# Motor_Control.net
KiCad netlist of a schematic drawn in Altium Designer
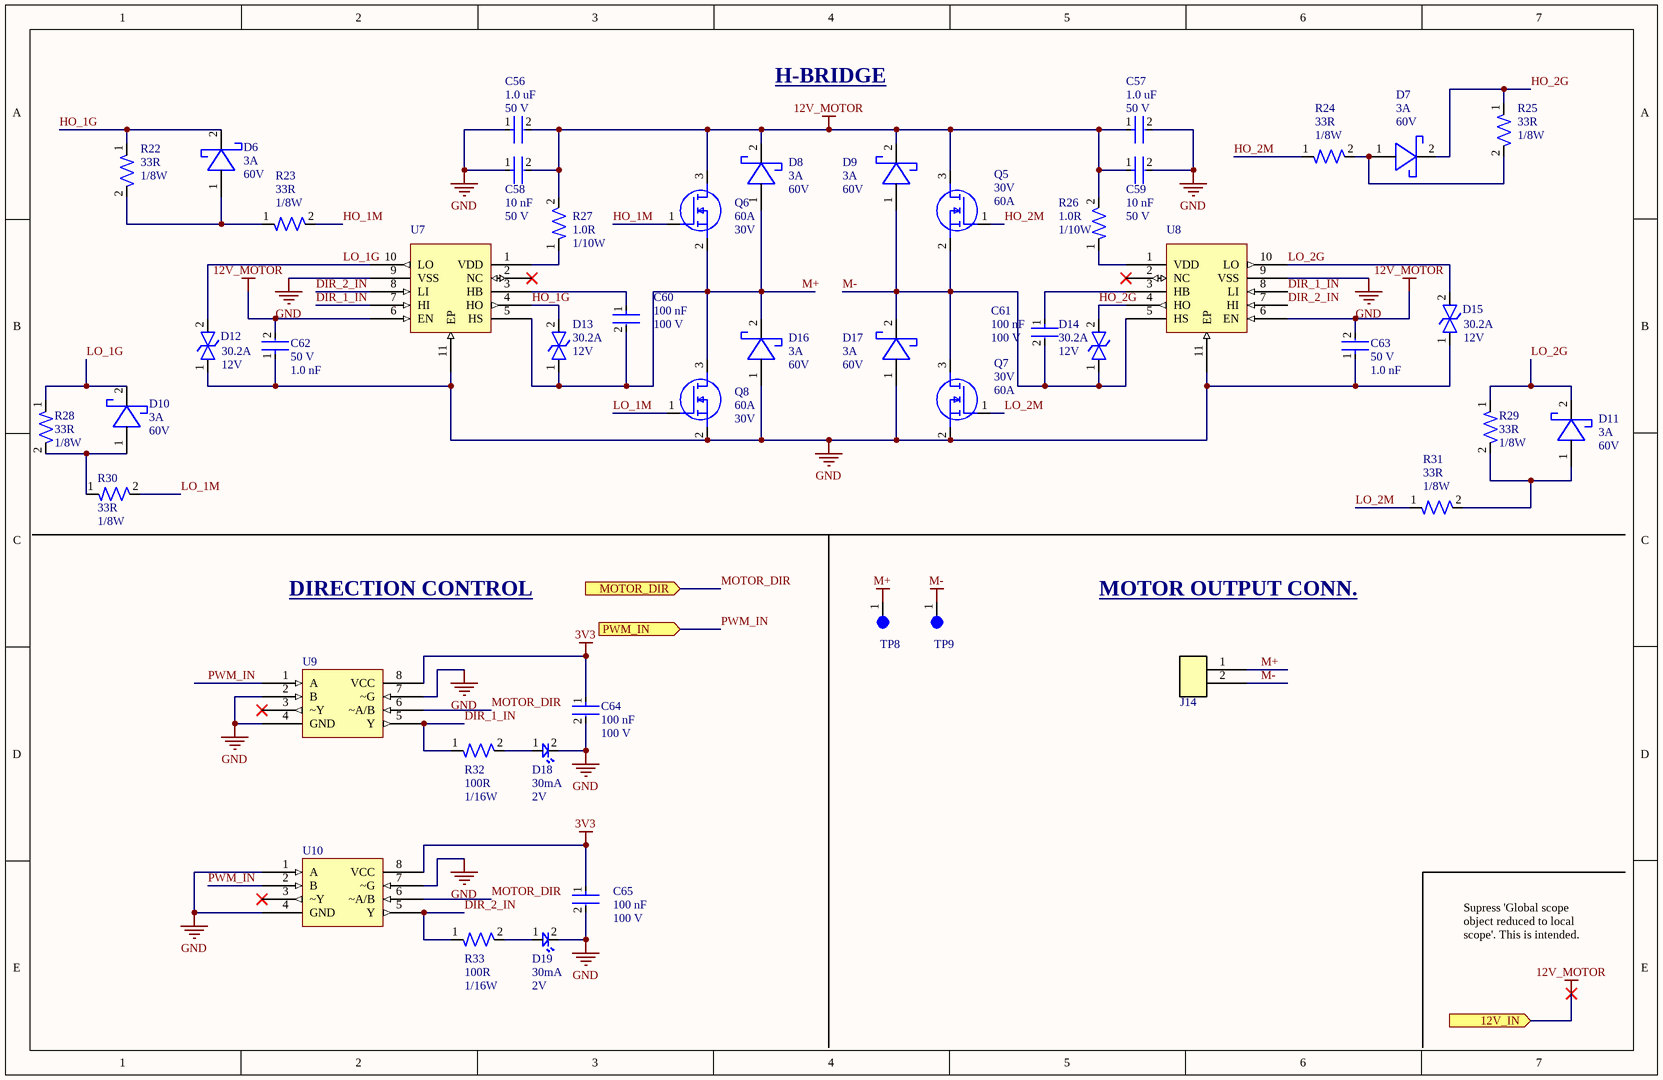
[diagram p0: Motor_Control.SchDoc]

(export (version "E")
  (design (tool "Eeschema 10.0.6"))
  (components
    (comp (ref "C56")
      (value "CC0805KKX7R9BB105")
      (footprint "CAP-0805")
      (description "CAP CER 1UF 50V X7R 0805")
      (fields (field (name "VOLTAGE") "50 V") (field (name "CAPACITANCE") "1.0 uF"))
      (libsource (lib "JLC_25") (part "CAP-1U-0001"))
    )
    (comp (ref "C57")
      (value "CC0805KKX7R9BB105")
      (footprint "CAP-0805")
      (description "CAP CER 1UF 50V X7R 0805")
      (fields (field (name "VOLTAGE") "50 V") (field (name "CAPACITANCE") "1.0 uF"))
      (libsource (lib "JLC_25") (part "CAP-1U-0001"))
    )
    (comp (ref "C58")
      (value "CC0603KPX7R9BB103")
      (footprint "CAP-0603")
      (description "CAP CER 10000PF 50V X7R 0603")
      (fields (field (name "VOLTAGE") "50 V") (field (name "CAPACITANCE") "10 nF"))
      (libsource (lib "JLC_25") (part "CAP-10N-0002"))
    )
    (comp (ref "C59")
      (value "CC0603KPX7R9BB103")
      (footprint "CAP-0603")
      (description "CAP CER 10000PF 50V X7R 0603")
      (fields (field (name "VOLTAGE") "50 V") (field (name "CAPACITANCE") "10 nF"))
      (libsource (lib "JLC_25") (part "CAP-10N-0002"))
    )
    (comp (ref "C60")
      (value "CC0603KRX7R0BB104")
      (footprint "CAP-0603")
      (description "CAP CER 0.1UF 100V X7R 0603")
      (fields (field (name "CAPACITANCE") "100 nF") (field (name "VOLTAGE") "100 V"))
      (libsource (lib "JLC_25") (part "CAP-100N-0001"))
    )
    (comp (ref "C61")
      (value "CC0603KRX7R0BB104")
      (footprint "CAP-0603")
      (description "CAP CER 0.1UF 100V X7R 0603")
      (fields (field (name "CAPACITANCE") "100 nF") (field (name "VOLTAGE") "100 V"))
      (libsource (lib "JLC_25") (part "CAP-100N-0001"))
    )
    (comp (ref "C62")
      (value "CC0402KRX7R9BB102")
      (footprint "CAP-0402")
      (description "CAP CER 1000PF 50V X7R 0402")
      (fields (field (name "VOLTAGE") "50 V") (field (name "CAPACITANCE") "1.0 nF"))
      (libsource (lib "JLC_25") (part "CAP-1N-0001"))
    )
    (comp (ref "C63")
      (value "CC0402KRX7R9BB102")
      (footprint "CAP-0402")
      (description "CAP CER 1000PF 50V X7R 0402")
      (fields (field (name "VOLTAGE") "50 V") (field (name "CAPACITANCE") "1.0 nF"))
      (libsource (lib "JLC_25") (part "CAP-1N-0001"))
    )
    (comp (ref "C64")
      (value "CC0603KRX7R0BB104")
      (footprint "CAP-0603")
      (description "CAP CER 0.1UF 100V X7R 0603")
      (fields (field (name "CAPACITANCE") "100 nF") (field (name "VOLTAGE") "100 V"))
      (libsource (lib "JLC_25") (part "CAP-100N-0001"))
    )
    (comp (ref "C65")
      (value "CC0603KRX7R0BB104")
      (footprint "CAP-0603")
      (description "CAP CER 0.1UF 100V X7R 0603")
      (fields (field (name "CAPACITANCE") "100 nF") (field (name "VOLTAGE") "100 V"))
      (libsource (lib "JLC_25") (part "CAP-100N-0001"))
    )
    (comp (ref "D6")
      (value "PMEG6030EP,115")
      (footprint "DIO-SOD128")
      (description "DIODE SCHOTTKY 60V 3A SOD128")
      (fields (field (name "CURRENT RATING") "3A") (field (name "REVERSE VOLTAGE") "60V"))
      (libsource (lib "JLC_25") (part "DIO-SCHOTTKY-0003"))
    )
    (comp (ref "D7")
      (value "PMEG6030EP,115")
      (footprint "DIO-SOD128")
      (description "DIODE SCHOTTKY 60V 3A SOD128")
      (fields (field (name "CURRENT RATING") "3A") (field (name "REVERSE VOLTAGE") "60V"))
      (libsource (lib "JLC_25") (part "DIO-SCHOTTKY-0003"))
    )
    (comp (ref "D8")
      (value "PMEG6030EP,115")
      (footprint "DIO-SOD128")
      (description "DIODE SCHOTTKY 60V 3A SOD128")
      (fields (field (name "CURRENT RATING") "3A") (field (name "REVERSE VOLTAGE") "60V"))
      (libsource (lib "JLC_25") (part "DIO-SCHOTTKY-0003"))
    )
    (comp (ref "D9")
      (value "PMEG6030EP,115")
      (footprint "DIO-SOD128")
      (description "DIODE SCHOTTKY 60V 3A SOD128")
      (fields (field (name "CURRENT RATING") "3A") (field (name "REVERSE VOLTAGE") "60V"))
      (libsource (lib "JLC_25") (part "DIO-SCHOTTKY-0003"))
    )
    (comp (ref "D10")
      (value "PMEG6030EP,115")
      (footprint "DIO-SOD128")
      (description "DIODE SCHOTTKY 60V 3A SOD128")
      (fields (field (name "CURRENT RATING") "3A") (field (name "REVERSE VOLTAGE") "60V"))
      (libsource (lib "JLC_25") (part "DIO-SCHOTTKY-0003"))
    )
    (comp (ref "D11")
      (value "PMEG6030EP,115")
      (footprint "DIO-SOD128")
      (description "DIODE SCHOTTKY 60V 3A SOD128")
      (fields (field (name "CURRENT RATING") "3A") (field (name "REVERSE VOLTAGE") "60V"))
      (libsource (lib "JLC_25") (part "DIO-SCHOTTKY-0003"))
    )
    (comp (ref "D12")
      (value "SMBJ12CA")
      (footprint "DO-214AA (SMBJ)")
      (description "TVS DIODE 12VWM 19.9VC DO214AA")
      (fields (field (name "STANDOFF VOLTAGE") "12V") (field (name "CURRENT RATING") "30.2A"))
      (libsource (lib "JLC_25") (part "DIO-TVS-0002"))
    )
    (comp (ref "D13")
      (value "SMBJ12CA")
      (footprint "DO-214AA (SMBJ)")
      (description "TVS DIODE 12VWM 19.9VC DO214AA")
      (fields (field (name "STANDOFF VOLTAGE") "12V") (field (name "CURRENT RATING") "30.2A"))
      (libsource (lib "JLC_25") (part "DIO-TVS-0002"))
    )
    (comp (ref "D14")
      (value "SMBJ12CA")
      (footprint "DO-214AA (SMBJ)")
      (description "TVS DIODE 12VWM 19.9VC DO214AA")
      (fields (field (name "STANDOFF VOLTAGE") "12V") (field (name "CURRENT RATING") "30.2A"))
      (libsource (lib "JLC_25") (part "DIO-TVS-0002"))
    )
    (comp (ref "D15")
      (value "SMBJ12CA")
      (footprint "DO-214AA (SMBJ)")
      (description "TVS DIODE 12VWM 19.9VC DO214AA")
      (fields (field (name "STANDOFF VOLTAGE") "12V") (field (name "CURRENT RATING") "30.2A"))
      (libsource (lib "JLC_25") (part "DIO-TVS-0002"))
    )
    (comp (ref "D16")
      (value "PMEG6030EP,115")
      (footprint "DIO-SOD128")
      (description "DIODE SCHOTTKY 60V 3A SOD128")
      (fields (field (name "CURRENT RATING") "3A") (field (name "REVERSE VOLTAGE") "60V"))
      (libsource (lib "JLC_25") (part "DIO-SCHOTTKY-0003"))
    )
    (comp (ref "D17")
      (value "PMEG6030EP,115")
      (footprint "DIO-SOD128")
      (description "DIODE SCHOTTKY 60V 3A SOD128")
      (fields (field (name "CURRENT RATING") "3A") (field (name "REVERSE VOLTAGE") "60V"))
      (libsource (lib "JLC_25") (part "DIO-SCHOTTKY-0003"))
    )
    (comp (ref "D18")
      (value "BL-HKC36G-AV-TRB")
      (footprint "LED-0603")
      (description "LED YELLOW CLEAR 0603 SMD")
      (fields (field (name "FORWARD CURRENT") "30mA") (field (name "FORWARD VOLTAGE") "2V"))
      (libsource (lib "JLC_25") (part "LED-0001"))
    )
    (comp (ref "D19")
      (value "BL-HKC36G-AV-TRB")
      (footprint "LED-0603")
      (description "LED YELLOW CLEAR 0603 SMD")
      (fields (field (name "FORWARD CURRENT") "30mA") (field (name "FORWARD VOLTAGE") "2V"))
      (libsource (lib "JLC_25") (part "LED-0001"))
    )
    (comp (ref "J14")
      (value "0430450212")
      (footprint "CONN-2POS-0001")
      (description "CONN HEADER VERT 2POS")
      (libsource (lib "JLC_25") (part "CONN-2POS-0001"))
    )
    (comp (ref "Q5")
      (value "CSD17575Q3")
      (footprint "IC-8VSONCLIP")
      (description "MOSFET N-CH 30V 60A 8VSON")
      (fields (field (name "VOLTAGE") "30V") (field (name "CONTINUOUS CURRENT") "60A"))
      (libsource (lib "JLC_25") (part "NMOS-26A-0001"))
    )
    (comp (ref "Q6")
      (value "CSD17575Q3")
      (footprint "IC-8VSONCLIP")
      (description "MOSFET N-CH 30V 60A 8VSON")
      (fields (field (name "VOLTAGE") "30V") (field (name "CONTINUOUS CURRENT") "60A"))
      (libsource (lib "JLC_25") (part "NMOS-26A-0001"))
    )
    (comp (ref "Q7")
      (value "CSD17575Q3")
      (footprint "IC-8VSONCLIP")
      (description "MOSFET N-CH 30V 60A 8VSON")
      (fields (field (name "VOLTAGE") "30V") (field (name "CONTINUOUS CURRENT") "60A"))
      (libsource (lib "JLC_25") (part "NMOS-26A-0001"))
    )
    (comp (ref "Q8")
      (value "CSD17575Q3")
      (footprint "IC-8VSONCLIP")
      (description "MOSFET N-CH 30V 60A 8VSON")
      (fields (field (name "VOLTAGE") "30V") (field (name "CONTINUOUS CURRENT") "60A"))
      (libsource (lib "JLC_25") (part "NMOS-26A-0001"))
    )
    (comp (ref "R22")
      (value "RC0402FR-7W33RL")
      (footprint "RES-0402")
      (description "RES 33 OHM 1% 1/8W 0402")
      (fields (field (name "TOLERANCE") "1%") (field (name "RESISTANCE") "33R") (field (name "POWER") "1/8W"))
      (libsource (lib "JLC_25") (part "RES-33-0001"))
    )
    (comp (ref "R23")
      (value "RC0402FR-7W33RL")
      (footprint "RES-0402")
      (description "RES 33 OHM 1% 1/8W 0402")
      (fields (field (name "TOLERANCE") "1%") (field (name "RESISTANCE") "33R") (field (name "POWER") "1/8W"))
      (libsource (lib "JLC_25") (part "RES-33-0001"))
    )
    (comp (ref "R24")
      (value "RC0402FR-7W33RL")
      (footprint "RES-0402")
      (description "RES 33 OHM 1% 1/8W 0402")
      (fields (field (name "TOLERANCE") "1%") (field (name "RESISTANCE") "33R") (field (name "POWER") "1/8W"))
      (libsource (lib "JLC_25") (part "RES-33-0001"))
    )
    (comp (ref "R25")
      (value "RC0402FR-7W33RL")
      (footprint "RES-0402")
      (description "RES 33 OHM 1% 1/8W 0402")
      (fields (field (name "TOLERANCE") "1%") (field (name "RESISTANCE") "33R") (field (name "POWER") "1/8W"))
      (libsource (lib "JLC_25") (part "RES-33-0001"))
    )
    (comp (ref "R26")
      (value "ERJ2GEJ1R0X")
      (footprint "RES-0402")
      (description "RES SMD 1 OHM 5% 1/10W 0402")
      (fields
        (field (name "TOLERANCE") "5%")
        (field (name "RESISTANCE") "1.0R")
        (field (name "POWER") "1/10W")
      )
      (libsource (lib "JLC_25") (part "RES-1-0001"))
    )
    (comp (ref "R27")
      (value "ERJ2GEJ1R0X")
      (footprint "RES-0402")
      (description "RES SMD 1 OHM 5% 1/10W 0402")
      (fields
        (field (name "TOLERANCE") "5%")
        (field (name "RESISTANCE") "1.0R")
        (field (name "POWER") "1/10W")
      )
      (libsource (lib "JLC_25") (part "RES-1-0001"))
    )
    (comp (ref "R28")
      (value "RC0402FR-7W33RL")
      (footprint "RES-0402")
      (description "RES 33 OHM 1% 1/8W 0402")
      (fields (field (name "TOLERANCE") "1%") (field (name "RESISTANCE") "33R") (field (name "POWER") "1/8W"))
      (libsource (lib "JLC_25") (part "RES-33-0001"))
    )
    (comp (ref "R29")
      (value "RC0402FR-7W33RL")
      (footprint "RES-0402")
      (description "RES 33 OHM 1% 1/8W 0402")
      (fields (field (name "TOLERANCE") "1%") (field (name "RESISTANCE") "33R") (field (name "POWER") "1/8W"))
      (libsource (lib "JLC_25") (part "RES-33-0001"))
    )
    (comp (ref "R30")
      (value "RC0402FR-7W33RL")
      (footprint "RES-0402")
      (description "RES 33 OHM 1% 1/8W 0402")
      (fields (field (name "TOLERANCE") "1%") (field (name "RESISTANCE") "33R") (field (name "POWER") "1/8W"))
      (libsource (lib "JLC_25") (part "RES-33-0001"))
    )
    (comp (ref "R31")
      (value "RC0402FR-7W33RL")
      (footprint "RES-0402")
      (description "RES 33 OHM 1% 1/8W 0402")
      (fields (field (name "TOLERANCE") "1%") (field (name "RESISTANCE") "33R") (field (name "POWER") "1/8W"))
      (libsource (lib "JLC_25") (part "RES-33-0001"))
    )
    (comp (ref "R32")
      (value "RC0402FR-07100RL")
      (footprint "RES-0402")
      (description "RES 100 OHM 1% 1/16W 0402")
      (fields
        (field (name "TOLERANCE") "1%")
        (field (name "POWER") "1/16W")
        (field (name "RESISTANCE") "100R")
      )
      (libsource (lib "JLC_25") (part "RES-100-0001"))
    )
    (comp (ref "R33")
      (value "RC0402FR-07100RL")
      (footprint "RES-0402")
      (description "RES 100 OHM 1% 1/16W 0402")
      (fields
        (field (name "TOLERANCE") "1%")
        (field (name "POWER") "1/16W")
        (field (name "RESISTANCE") "100R")
      )
      (libsource (lib "JLC_25") (part "RES-100-0001"))
    )
    (comp (ref "TP8")
      (value "5003")
      (footprint "TEST-POINT-0001")
      (description "Oranange PC Test Point, Miniature Phoisphor Bronze Silver Plating Through Hole Mounting Type")
      (libsource (lib "*") (part "TEST-POINT-0001"))
    )
    (comp (ref "TP9")
      (value "5003")
      (footprint "TEST-POINT-0001")
      (description "Oranange PC Test Point, Miniature Phoisphor Bronze Silver Plating Through Hole Mounting Type")
      (libsource (lib "*") (part "TEST-POINT-0001"))
    )
    (comp (ref "U7")
      (value "UCC27282DRCR")
      (footprint "IC-10VSON")
      (description "IC GATE DRVR HALF-BRIDGE 10VSON")
      (libsource (lib "") (part "IC-GTDR-0001_1"))
    )
    (comp (ref "U8")
      (value "UCC27282DRCR")
      (footprint "IC-10VSON")
      (description "IC GATE DRVR HALF-BRIDGE 10VSON")
      (libsource (lib "JLC_25") (part "IC-GTDR-0001"))
    )
    (comp (ref "U9")
      (value "SN74LVC2G157DCUR")
      (footprint "IC-8VSSOP")
      (description "Multiplexer 1 x 2:1 8-VSSOP")
      (libsource (lib "JLC_25") (part "IC-MUX-0001"))
    )
    (comp (ref "U10")
      (value "SN74LVC2G157DCUR")
      (footprint "IC-8VSSOP")
      (description "Multiplexer 1 x 2:1 8-VSSOP")
      (libsource (lib "JLC_25") (part "IC-MUX-0001"))
    )
  )
  (nets
    (net (code "1") (name "/DIR_1_IN") (class "Default")
      (node (ref "R32") (pin "1") (pinfunction "1_1") (pintype "passive"))
      (node (ref "U7") (pin "7") (pinfunction "HI_7") (pintype "input"))
      (node (ref "U8") (pin "8") (pinfunction "LI_8") (pintype "input"))
      (node (ref "U9") (pin "5") (pinfunction "Y_5") (pintype "output"))
    )
    (net (code "2") (name "/DIR_2_IN") (class "Default")
      (node (ref "R33") (pin "1") (pinfunction "1_1") (pintype "passive"))
      (node (ref "U10") (pin "5") (pinfunction "Y_5") (pintype "output"))
      (node (ref "U7") (pin "8") (pinfunction "LI_8") (pintype "input"))
      (node (ref "U8") (pin "7") (pinfunction "HI_7") (pintype "input"))
    )
    (net (code "3") (name "/HO_1G") (class "Default")
      (node (ref "D13") (pin "2") (pintype "passive"))
      (node (ref "D6") (pin "2") (pinfunction "ANODE_2") (pintype "passive"))
      (node (ref "R22") (pin "1") (pinfunction "1_1") (pintype "passive"))
      (node (ref "U7") (pin "4") (pinfunction "HO_4") (pintype "output"))
    )
    (net (code "4") (name "/HO_1M") (class "Default")
      (node (ref "Q6") (pin "1") (pinfunction "G_1") (pintype "passive"))
      (node (ref "R23") (pin "2") (pinfunction "2_2") (pintype "passive"))
    )
    (net (code "5") (name "/HO_2G") (class "Default")
      (node (ref "D14") (pin "2") (pintype "passive"))
      (node (ref "D7") (pin "2") (pinfunction "ANODE_2") (pintype "passive"))
      (node (ref "R25") (pin "1") (pinfunction "1_1") (pintype "passive"))
      (node (ref "U8") (pin "4") (pinfunction "HO_4") (pintype "output"))
    )
    (net (code "6") (name "/HO_2M") (class "Default")
      (node (ref "Q5") (pin "1") (pinfunction "G_1") (pintype "passive"))
      (node (ref "R24") (pin "1") (pinfunction "1_1") (pintype "passive"))
    )
    (net (code "7") (name "/LO_1G") (class "Default")
      (node (ref "D10") (pin "2") (pinfunction "ANODE_2") (pintype "passive"))
      (node (ref "D12") (pin "2") (pintype "passive"))
      (node (ref "R28") (pin "1") (pinfunction "1_1") (pintype "passive"))
      (node (ref "U7") (pin "10") (pinfunction "LO_10") (pintype "output"))
    )
    (net (code "8") (name "/LO_1M") (class "Default")
      (node (ref "Q8") (pin "1") (pinfunction "G_1") (pintype "passive"))
      (node (ref "R30") (pin "2") (pinfunction "2_2") (pintype "passive"))
    )
    (net (code "9") (name "/LO_2G") (class "Default")
      (node (ref "D11") (pin "2") (pinfunction "ANODE_2") (pintype "passive"))
      (node (ref "D15") (pin "2") (pintype "passive"))
      (node (ref "R29") (pin "1") (pinfunction "1_1") (pintype "passive"))
      (node (ref "U8") (pin "10") (pinfunction "LO_10") (pintype "output"))
    )
    (net (code "10") (name "/LO_2M") (class "Default")
      (node (ref "Q7") (pin "1") (pinfunction "G_1") (pintype "passive"))
      (node (ref "R31") (pin "1") (pinfunction "1_1") (pintype "passive"))
    )
    (net (code "11") (name "/MOTOR_DIR") (class "Default")
      (node (ref "U10") (pin "6") (pinfunction "~A/B_6") (pintype "input"))
      (node (ref "U9") (pin "6") (pinfunction "~A/B_6") (pintype "input"))
    )
    (net (code "12") (name "/PWM_IN") (class "Default")
      (node (ref "U10") (pin "2") (pinfunction "B_2") (pintype "input"))
      (node (ref "U9") (pin "1") (pinfunction "A_1") (pintype "input"))
    )
    (net (code "13") (name "3V3") (class "Default")
      (node (ref "C64") (pin "1") (pinfunction "1_1") (pintype "passive"))
      (node (ref "C65") (pin "1") (pinfunction "1_1") (pintype "passive"))
      (node (ref "U10") (pin "8") (pinfunction "VCC_8") (pintype "power_in"))
      (node (ref "U9") (pin "8") (pinfunction "VCC_8") (pintype "power_in"))
    )
    (net (code "14") (name "12V_MOTOR") (class "Default")
      (node (ref "C56") (pin "2") (pinfunction "2_2") (pintype "passive"))
      (node (ref "C57") (pin "1") (pinfunction "1_1") (pintype "passive"))
      (node (ref "C58") (pin "2") (pinfunction "2_2") (pintype "passive"))
      (node (ref "C59") (pin "1") (pinfunction "1_1") (pintype "passive"))
      (node (ref "C62") (pin "2") (pinfunction "2_2") (pintype "passive"))
      (node (ref "C63") (pin "2") (pinfunction "2_2") (pintype "passive"))
      (node (ref "D8") (pin "2") (pinfunction "ANODE_2") (pintype "passive"))
      (node (ref "D9") (pin "2") (pinfunction "ANODE_2") (pintype "passive"))
      (node (ref "Q5") (pin "3") (pinfunction "D_3") (pintype "passive"))
      (node (ref "Q6") (pin "3") (pinfunction "D_3") (pintype "passive"))
      (node (ref "R26") (pin "2") (pinfunction "2_2") (pintype "passive"))
      (node (ref "R27") (pin "2") (pinfunction "2_2") (pintype "passive"))
      (node (ref "U7") (pin "6") (pinfunction "EN_6") (pintype "input"))
      (node (ref "U8") (pin "6") (pinfunction "EN_6") (pintype "input"))
    )
    (net (code "15") (name "GND") (class "Default")
      (node (ref "C56") (pin "1") (pinfunction "1_1") (pintype "passive"))
      (node (ref "C57") (pin "2") (pinfunction "2_2") (pintype "passive"))
      (node (ref "C58") (pin "1") (pinfunction "1_1") (pintype "passive"))
      (node (ref "C59") (pin "2") (pinfunction "2_2") (pintype "passive"))
      (node (ref "C62") (pin "1") (pinfunction "1_1") (pintype "passive"))
      (node (ref "C63") (pin "1") (pinfunction "1_1") (pintype "passive"))
      (node (ref "C64") (pin "2") (pinfunction "2_2") (pintype "passive"))
      (node (ref "C65") (pin "2") (pinfunction "2_2") (pintype "passive"))
      (node (ref "D12") (pin "1") (pintype "passive"))
      (node (ref "D15") (pin "1") (pintype "passive"))
      (node (ref "D16") (pin "1") (pinfunction "CATHODE_1") (pintype "passive"))
      (node (ref "D17") (pin "1") (pinfunction "CATHODE_1") (pintype "passive"))
      (node (ref "D18") (pin "2") (pinfunction "2_2") (pintype "passive"))
      (node (ref "D19") (pin "2") (pinfunction "2_2") (pintype "passive"))
      (node (ref "Q7") (pin "2") (pinfunction "S_2") (pintype "passive"))
      (node (ref "Q8") (pin "2") (pinfunction "S_2") (pintype "passive"))
      (node (ref "U10") (pin "1") (pinfunction "A_1") (pintype "input"))
      (node (ref "U10") (pin "4") (pinfunction "GND_4") (pintype "power_in"))
      (node (ref "U10") (pin "7") (pinfunction "~G_7") (pintype "input"))
      (node (ref "U7") (pin "11") (pinfunction "EP_11") (pintype "input"))
      (node (ref "U7") (pin "9") (pinfunction "VSS_9") (pintype "power_in"))
      (node (ref "U8") (pin "11") (pinfunction "EP_11") (pintype "input"))
      (node (ref "U8") (pin "9") (pinfunction "VSS_9") (pintype "power_in"))
      (node (ref "U9") (pin "2") (pinfunction "B_2") (pintype "input"))
      (node (ref "U9") (pin "4") (pinfunction "GND_4") (pintype "power_in"))
      (node (ref "U9") (pin "7") (pinfunction "~G_7") (pintype "input"))
    )
    (net (code "16") (name "M+") (class "Default")
      (node (ref "C60") (pin "2") (pinfunction "2_2") (pintype "passive"))
      (node (ref "D13") (pin "1") (pintype "passive"))
      (node (ref "D16") (pin "2") (pinfunction "ANODE_2") (pintype "passive"))
      (node (ref "D8") (pin "1") (pinfunction "CATHODE_1") (pintype "passive"))
      (node (ref "J14") (pin "1") (pinfunction "7_1") (pintype "passive"))
      (node (ref "Q6") (pin "2") (pinfunction "S_2") (pintype "passive"))
      (node (ref "Q8") (pin "3") (pinfunction "D_3") (pintype "passive"))
      (node (ref "TP8") (pin "1") (pinfunction "0_1") (pintype "passive"))
      (node (ref "U7") (pin "5") (pinfunction "HS_5") (pintype "power_in"))
    )
    (net (code "17") (name "M-") (class "Default")
      (node (ref "C61") (pin "2") (pinfunction "2_2") (pintype "passive"))
      (node (ref "D14") (pin "1") (pintype "passive"))
      (node (ref "D17") (pin "2") (pinfunction "ANODE_2") (pintype "passive"))
      (node (ref "D9") (pin "1") (pinfunction "CATHODE_1") (pintype "passive"))
      (node (ref "J14") (pin "2") (pinfunction "8_2") (pintype "passive"))
      (node (ref "Q5") (pin "2") (pinfunction "S_2") (pintype "passive"))
      (node (ref "Q7") (pin "3") (pinfunction "D_3") (pintype "passive"))
      (node (ref "TP9") (pin "1") (pinfunction "0_1") (pintype "passive"))
      (node (ref "U8") (pin "5") (pinfunction "HS_5") (pintype "power_in"))
    )
    (net (code "18") (name "Net-(D6-CATHODE)") (class "Default")
      (node (ref "D6") (pin "1") (pinfunction "CATHODE_1") (pintype "passive"))
      (node (ref "R22") (pin "2") (pinfunction "2_2") (pintype "passive"))
      (node (ref "R23") (pin "1") (pinfunction "1_1") (pintype "passive"))
    )
    (net (code "19") (name "Net-(D7-CATHODE)") (class "Default")
      (node (ref "D7") (pin "1") (pinfunction "CATHODE_1") (pintype "passive"))
      (node (ref "R24") (pin "2") (pinfunction "2_2") (pintype "passive"))
      (node (ref "R25") (pin "2") (pinfunction "2_2") (pintype "passive"))
    )
    (net (code "20") (name "Net-(D10-CATHODE)") (class "Default")
      (node (ref "D10") (pin "1") (pinfunction "CATHODE_1") (pintype "passive"))
      (node (ref "R28") (pin "2") (pinfunction "2_2") (pintype "passive"))
      (node (ref "R30") (pin "1") (pinfunction "1_1") (pintype "passive"))
    )
    (net (code "21") (name "Net-(D11-CATHODE)") (class "Default")
      (node (ref "D11") (pin "1") (pinfunction "CATHODE_1") (pintype "passive"))
      (node (ref "R29") (pin "2") (pinfunction "2_2") (pintype "passive"))
      (node (ref "R31") (pin "2") (pinfunction "2_2") (pintype "passive"))
    )
    (net (code "22") (name "Net-(D18-Pad1)") (class "Default")
      (node (ref "D18") (pin "1") (pinfunction "1_1") (pintype "passive"))
      (node (ref "R32") (pin "2") (pinfunction "2_2") (pintype "passive"))
    )
    (net (code "23") (name "Net-(D19-Pad1)") (class "Default")
      (node (ref "D19") (pin "1") (pinfunction "1_1") (pintype "passive"))
      (node (ref "R33") (pin "2") (pinfunction "2_2") (pintype "passive"))
    )
    (net (code "24") (name "Net-(U7-HB)") (class "Default")
      (node (ref "C60") (pin "1") (pinfunction "1_1") (pintype "passive"))
      (node (ref "U7") (pin "3") (pinfunction "HB_3") (pintype "power_in"))
    )
    (net (code "25") (name "Net-(U7-VDD)") (class "Default")
      (node (ref "R27") (pin "1") (pinfunction "1_1") (pintype "passive"))
      (node (ref "U7") (pin "1") (pinfunction "VDD_1") (pintype "power_in"))
    )
    (net (code "26") (name "Net-(U8-HB)") (class "Default")
      (node (ref "C61") (pin "1") (pinfunction "1_1") (pintype "passive"))
      (node (ref "U8") (pin "3") (pinfunction "HB_3") (pintype "power_in"))
    )
    (net (code "27") (name "Net-(U8-VDD)") (class "Default")
      (node (ref "R26") (pin "1") (pinfunction "1_1") (pintype "passive"))
      (node (ref "U8") (pin "1") (pinfunction "VDD_1") (pintype "power_in"))
    )
    (net (code "28") (name "unconnected-(U7-NC-Pad2)") (class "Default")
      (node (ref "U7") (pin "2") (pinfunction "NC_2") (pintype "bidirectional+no_connect"))
    )
    (net (code "29") (name "unconnected-(U8-NC-Pad2)") (class "Default")
      (node (ref "U8") (pin "2") (pinfunction "NC_2") (pintype "bidirectional+no_connect"))
    )
    (net (code "30") (name "unconnected-(U9-~Y-Pad3)") (class "Default")
      (node (ref "U9") (pin "3") (pinfunction "~Y_3") (pintype "output+no_connect"))
    )
    (net (code "31") (name "unconnected-(U10-~Y-Pad3)") (class "Default")
      (node (ref "U10") (pin "3") (pinfunction "~Y_3") (pintype "output+no_connect"))
    )
  )
)
